# pay-ssm.net
KiCad netlist of a schematic drawn in Altium Designer
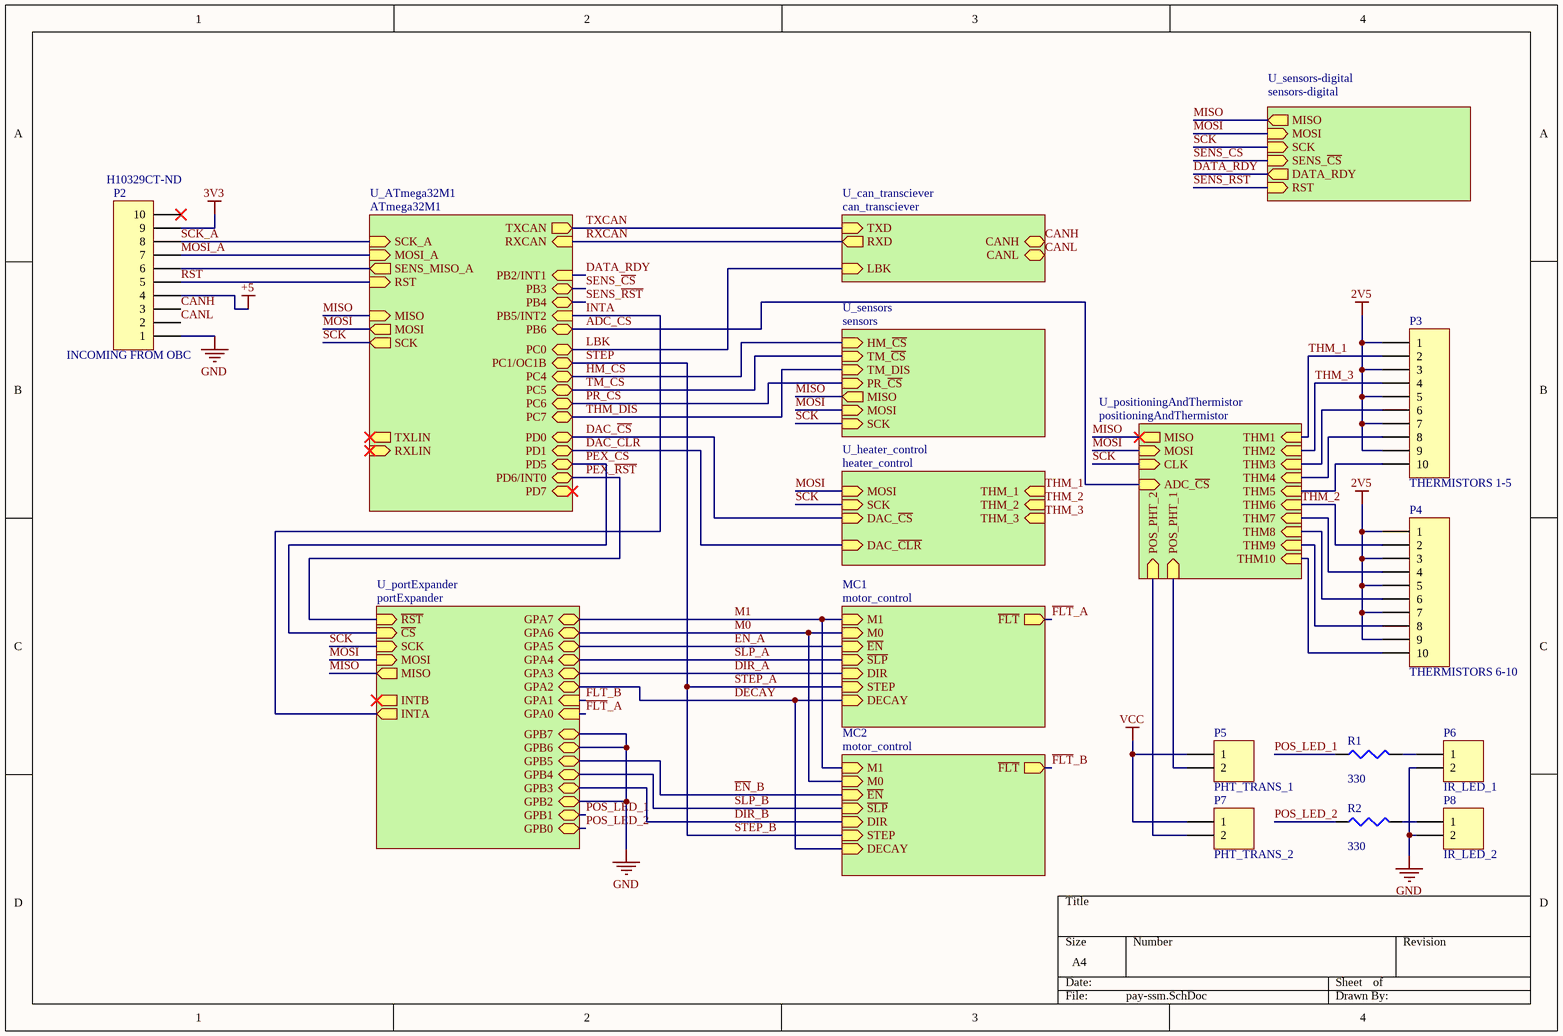
[diagram p0: pay-ssm.SchDoc]

(export (version "E")
  (design (tool "Eeschema 10.0.6"))
  (components
    (comp (ref "P2")
      (value "INCOMING FROM OBC")
      (footprint "DF14-10P-1.25H(55)")
      (description "Header, 10-Pin")
      (fields (field (name "SUPPLIER PART NUMBER") "H10329CT-ND") (field (name "PUBLISHER") "Altium Limited"))
      (libsource (lib "Miscellaneous Connectors") (part "Header 10"))
    )
    (comp (ref "P3")
      (value "THERMISTORS 1-5")
      (footprint "DF14-10P-1.25H(55)")
      (description "Header, 10-Pin")
      (fields (field (name "PUBLISHER") "Altium Limited"))
      (libsource (lib "") (part "Header 10_1"))
    )
    (comp (ref "P4")
      (value "THERMISTORS 6-10")
      (footprint "DF14-10P-1.25H(55)")
      (description "Header, 10-Pin")
      (fields (field (name "PUBLISHER") "Altium Limited"))
      (libsource (lib "") (part "Header 10_1"))
    )
    (comp (ref "P5")
      (value "PHT_TRANS_1")
      (footprint "DF14-2P-1.25H(55)")
      (description "Header, 2-Pin")
      (fields (field (name "PUBLISHER") "Altium Limited"))
      (libsource (lib "Miscellaneous Connectors") (part "Header 2"))
    )
    (comp (ref "P6")
      (value "IR_LED_1")
      (footprint "DF14-2P-1.25H(55)")
      (description "Header, 2-Pin")
      (fields (field (name "PUBLISHER") "Altium Limited"))
      (libsource (lib "Miscellaneous Connectors") (part "Header 2"))
    )
    (comp (ref "P7")
      (value "PHT_TRANS_2")
      (footprint "DF14-2P-1.25H(55)")
      (description "Header, 2-Pin")
      (fields (field (name "PUBLISHER") "Altium Limited"))
      (libsource (lib "Miscellaneous Connectors") (part "Header 2"))
    )
    (comp (ref "P8")
      (value "IR_LED_2")
      (footprint "DF14-2P-1.25H(55)")
      (description "Header, 2-Pin")
      (fields (field (name "PUBLISHER") "Altium Limited"))
      (libsource (lib "Miscellaneous Connectors") (part "Header 2"))
    )
    (comp (ref "R1")
      (value "330")
      (footprint "J1-0603")
      (description "Resistor")
      (fields (field (name "PUBLISHER") "Altium Limited"))
      (libsource (lib "Miscellaneous Devices") (part "Res3"))
    )
    (comp (ref "R2")
      (value "330")
      (footprint "J1-0603")
      (description "Resistor")
      (fields (field (name "PUBLISHER") "Altium Limited"))
      (libsource (lib "Miscellaneous Devices") (part "Res3"))
    )
  )
  (nets
    (net (code "1") (name "+5") (class "Default")
      (node (ref "P2") (pin "4") (pinfunction "4_4") (pintype "passive"))
    )
    (net (code "3") (name "/CANH") (class "Default")
      (node (ref "P2") (pin "3") (pinfunction "3_3") (pintype "passive"))
    )
    (net (code "4") (name "/CANL") (class "Default")
      (node (ref "P2") (pin "2") (pinfunction "2_2") (pintype "passive"))
    )
    (net (code "19") (name "/MOSI_A") (class "Default")
      (node (ref "P2") (pin "7") (pinfunction "7_7") (pintype "passive"))
    )
    (net (code "23") (name "/POS_LED_1") (class "Default")
      (node (ref "R1") (pin "1") (pinfunction "1_1") (pintype "passive"))
    )
    (net (code "24") (name "/POS_LED_2") (class "Default")
      (node (ref "R2") (pin "1") (pinfunction "1_1") (pintype "passive"))
    )
    (net (code "25") (name "/POS_PHT_1") (class "Default")
      (node (ref "P5") (pin "2") (pinfunction "2_2") (pintype "passive"))
    )
    (net (code "26") (name "/POS_PHT_2") (class "Default")
      (node (ref "P7") (pin "2") (pinfunction "2_2") (pintype "passive"))
    )
    (net (code "31") (name "/SCK_A") (class "Default")
      (node (ref "P2") (pin "8") (pinfunction "8_8") (pintype "passive"))
    )
    (net (code "32") (name "/SENS_MISO_A") (class "Default")
      (node (ref "P2") (pin "6") (pinfunction "6_6") (pintype "passive"))
    )
    (net (code "36") (name "/THM3") (class "Default")
      (node (ref "P3") (pin "6") (pinfunction "6_6") (pintype "passive"))
    )
    (net (code "37") (name "/THM4") (class "Default")
      (node (ref "P3") (pin "8") (pinfunction "8_8") (pintype "passive"))
    )
    (net (code "38") (name "/THM5") (class "Default")
      (node (ref "P3") (pin "10") (pinfunction "10_10") (pintype "passive"))
    )
    (net (code "39") (name "/THM7") (class "Default")
      (node (ref "P4") (pin "4") (pinfunction "4_4") (pintype "passive"))
    )
    (net (code "40") (name "/THM8") (class "Default")
      (node (ref "P4") (pin "6") (pinfunction "6_6") (pintype "passive"))
    )
    (net (code "41") (name "/THM9") (class "Default")
      (node (ref "P4") (pin "8") (pinfunction "8_8") (pintype "passive"))
    )
    (net (code "42") (name "/THM10") (class "Default")
      (node (ref "P4") (pin "10") (pinfunction "10_10") (pintype "passive"))
    )
    (net (code "43") (name "/THM_1") (class "Default")
      (node (ref "P3") (pin "2") (pinfunction "2_2") (pintype "passive"))
    )
    (net (code "44") (name "/THM_2") (class "Default")
      (node (ref "P4") (pin "2") (pinfunction "2_2") (pintype "passive"))
    )
    (net (code "45") (name "/THM_3") (class "Default")
      (node (ref "P3") (pin "4") (pinfunction "4_4") (pintype "passive"))
    )
    (net (code "54") (name "/~{RST}") (class "Default")
      (node (ref "P2") (pin "5") (pinfunction "5_5") (pintype "passive"))
    )
    (net (code "57") (name "2V5") (class "Default")
      (node (ref "P3") (pin "1") (pinfunction "1_1") (pintype "passive"))
      (node (ref "P3") (pin "3") (pinfunction "3_3") (pintype "passive"))
      (node (ref "P3") (pin "5") (pinfunction "5_5") (pintype "passive"))
      (node (ref "P3") (pin "7") (pinfunction "7_7") (pintype "passive"))
      (node (ref "P3") (pin "9") (pinfunction "9_9") (pintype "passive"))
      (node (ref "P4") (pin "1") (pinfunction "1_1") (pintype "passive"))
      (node (ref "P4") (pin "3") (pinfunction "3_3") (pintype "passive"))
      (node (ref "P4") (pin "5") (pinfunction "5_5") (pintype "passive"))
      (node (ref "P4") (pin "7") (pinfunction "7_7") (pintype "passive"))
      (node (ref "P4") (pin "9") (pinfunction "9_9") (pintype "passive"))
    )
    (net (code "58") (name "3V3") (class "Default")
      (node (ref "P2") (pin "9") (pinfunction "9_9") (pintype "passive"))
    )
    (net (code "59") (name "GND") (class "Default")
      (node (ref "P2") (pin "1") (pinfunction "1_1") (pintype "passive"))
      (node (ref "P6") (pin "2") (pinfunction "2_2") (pintype "passive"))
      (node (ref "P8") (pin "2") (pinfunction "2_2") (pintype "passive"))
    )
    (net (code "60") (name "Net-(P6-Pad1)") (class "Default")
      (node (ref "P6") (pin "1") (pinfunction "1_1") (pintype "passive"))
      (node (ref "R1") (pin "2") (pinfunction "2_2") (pintype "passive"))
    )
    (net (code "61") (name "Net-(P8-Pad1)") (class "Default")
      (node (ref "P8") (pin "1") (pinfunction "1_1") (pintype "passive"))
      (node (ref "R2") (pin "2") (pinfunction "2_2") (pintype "passive"))
    )
    (net (code "62") (name "VCC") (class "Default")
      (node (ref "P5") (pin "1") (pinfunction "1_1") (pintype "passive"))
      (node (ref "P7") (pin "1") (pinfunction "1_1") (pintype "passive"))
    )
    (net (code "63") (name "unconnected-(P2-Pad10)") (class "Default")
      (node (ref "P2") (pin "10") (pinfunction "10_10") (pintype "passive+no_connect"))
    )
  )
)
